# fmc_digital_io_front_panel.net
KiCad netlist of a schematic drawn in Altium Designer
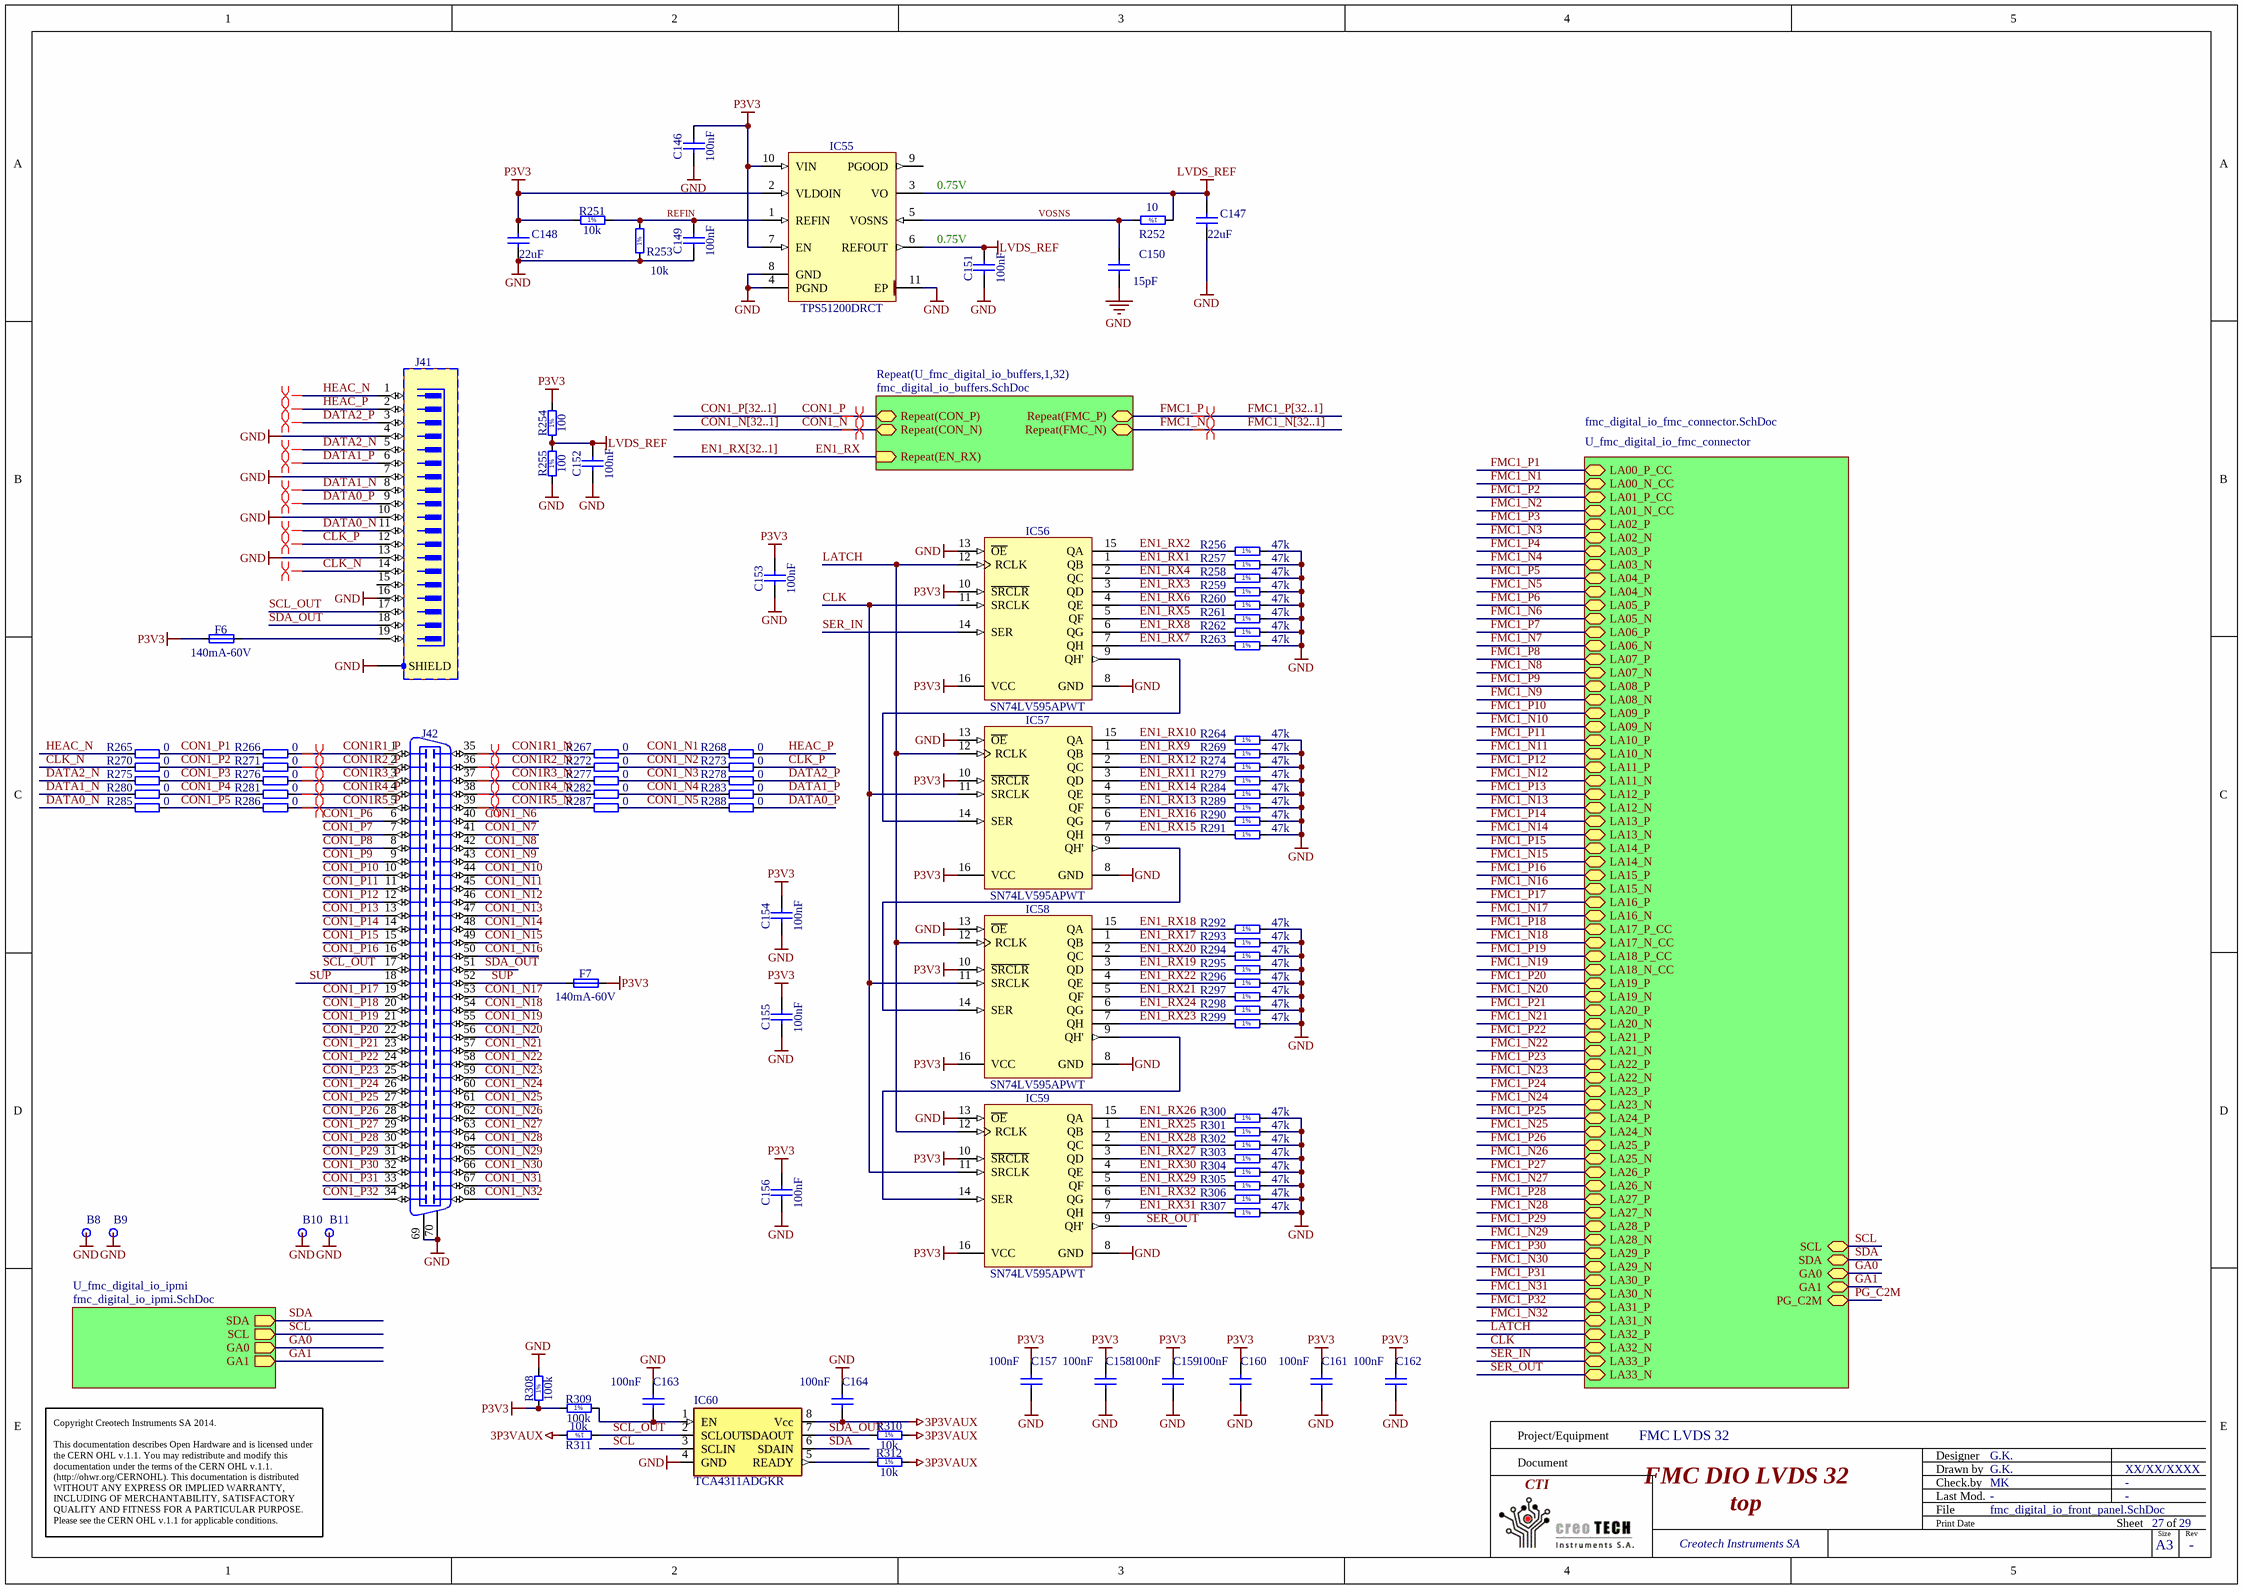
[diagram p0: fmc_digital_io_front_panel.SchDoc]

(export (version "E")
  (design (tool "Eeschema 10.0.6"))
  (components
    (comp (ref "B8")
      (value "Plated Hole")
      (footprint "MTG300_600")
      (description "Single Terminal Socket")
      (fields (field (name "PART NUMBER") "PLATED_HOLE3.0_PAD6.0") (field (name "AUTHOR") "CERN DEM JLC"))
      (libsource (lib "Eletro-mechanical") (part "Single Terminal Socket"))
    )
    (comp (ref "B9")
      (value "Plated Hole")
      (footprint "MTG300_600")
      (description "Single Terminal Socket")
      (fields (field (name "PART NUMBER") "PLATED_HOLE3.0_PAD6.0") (field (name "AUTHOR") "CERN DEM JLC"))
      (libsource (lib "Eletro-mechanical") (part "Single Terminal Socket"))
    )
    (comp (ref "B10")
      (value "Plated Hole")
      (footprint "MTG300_600")
      (description "Single Terminal Socket")
      (fields (field (name "PART NUMBER") "PLATED_HOLE3.0_PAD6.0") (field (name "AUTHOR") "CERN DEM JLC"))
      (libsource (lib "Eletro-mechanical") (part "Single Terminal Socket"))
    )
    (comp (ref "B11")
      (value "Plated Hole")
      (footprint "MTG300_600")
      (description "Single Terminal Socket")
      (fields (field (name "PART NUMBER") "PLATED_HOLE3.0_PAD6.0") (field (name "AUTHOR") "CERN DEM JLC"))
      (libsource (lib "Eletro-mechanical") (part "Single Terminal Socket"))
    )
    (comp (ref "C146")
      (value "100nF")
      (footprint "CAPC1005X55N")
      (description "Non-polarised capacitor")
      (fields
        (field (name "PART NUMBER") "CC0402_100NF_16V_10%_X5R")
        (field (name "VOLTAGE") "16V")
        (field (name "AUTHOR") "CERN DEM JLC")
      )
      (libsource (lib "Capacitors") (part "Capacitor - non polarized"))
    )
    (comp (ref "C147")
      (value "22uF")
      (footprint "CAPC3216X180N")
      (description "Non-polarised capacitor")
      (fields
        (field (name "PART NUMBER") "CC1206_22UF_10V_10%_X7R")
        (field (name "VOLTAGE") "10V")
        (field (name "AUTHOR") "CERN DEM JLC")
      )
      (libsource (lib "Capacitors") (part "Capacitor - non polarized"))
    )
    (comp (ref "C148")
      (value "22uF")
      (footprint "CAPC3216X180N")
      (description "Non-polarised capacitor")
      (fields
        (field (name "PART NUMBER") "CC1206_22UF_10V_10%_X7R")
        (field (name "VOLTAGE") "10V")
        (field (name "AUTHOR") "CERN DEM JLC")
      )
      (libsource (lib "Capacitors") (part "Capacitor - non polarized"))
    )
    (comp (ref "C149")
      (value "100nF")
      (footprint "CAPC1005X55N")
      (description "Non-polarised capacitor")
      (fields
        (field (name "PART NUMBER") "CC0402_100NF_16V_10%_X5R")
        (field (name "VOLTAGE") "16V")
        (field (name "AUTHOR") "CERN DEM JLC")
      )
      (libsource (lib "Capacitors") (part "Capacitor - non polarized"))
    )
    (comp (ref "C150")
      (value "15pF")
      (footprint "CAPC1005X55N")
      (description "Non-polarised capacitor")
      (fields
        (field (name "PART NUMBER") "CC0402_15PF_50V_5%_NP0")
        (field (name "VOLTAGE") "50V")
        (field (name "AUTHOR") "CERN DEM JLC")
      )
      (libsource (lib "Capacitors") (part "Capacitor - non polarized"))
    )
    (comp (ref "C151")
      (value "100nF")
      (footprint "CAPC1005X55N")
      (description "Non-polarised capacitor")
      (fields
        (field (name "PART NUMBER") "CC0402_100NF_16V_10%_X5R")
        (field (name "VOLTAGE") "16V")
        (field (name "AUTHOR") "CERN DEM JLC")
      )
      (libsource (lib "Capacitors") (part "Capacitor - non polarized"))
    )
    (comp (ref "C152")
      (value "100nF")
      (footprint "CAPC1005X55N")
      (description "Non-polarised capacitor")
      (fields
        (field (name "PART NUMBER") "CC0402_100NF_16V_10%_X5R")
        (field (name "VOLTAGE") "16V")
        (field (name "AUTHOR") "CERN DEM JLC")
      )
      (libsource (lib "Capacitors") (part "Capacitor - non polarized"))
    )
    (comp (ref "C153")
      (value "100nF")
      (footprint "CAPC1005X55N")
      (description "Non-polarised capacitor")
      (fields
        (field (name "PART NUMBER") "CC0402_100NF_16V_10%_X5R")
        (field (name "VOLTAGE") "16V")
        (field (name "AUTHOR") "CERN DEM JLC")
      )
      (libsource (lib "Capacitors") (part "Capacitor - non polarized"))
    )
    (comp (ref "C154")
      (value "100nF")
      (footprint "CAPC1005X55N")
      (description "Non-polarised capacitor")
      (fields
        (field (name "PART NUMBER") "CC0402_100NF_16V_10%_X5R")
        (field (name "VOLTAGE") "16V")
        (field (name "AUTHOR") "CERN DEM JLC")
      )
      (libsource (lib "Capacitors") (part "Capacitor - non polarized"))
    )
    (comp (ref "C155")
      (value "100nF")
      (footprint "CAPC1005X55N")
      (description "Non-polarised capacitor")
      (fields
        (field (name "PART NUMBER") "CC0402_100NF_16V_10%_X5R")
        (field (name "VOLTAGE") "16V")
        (field (name "AUTHOR") "CERN DEM JLC")
      )
      (libsource (lib "Capacitors") (part "Capacitor - non polarized"))
    )
    (comp (ref "C156")
      (value "100nF")
      (footprint "CAPC1005X55N")
      (description "Non-polarised capacitor")
      (fields
        (field (name "PART NUMBER") "CC0402_100NF_16V_10%_X5R")
        (field (name "VOLTAGE") "16V")
        (field (name "AUTHOR") "CERN DEM JLC")
      )
      (libsource (lib "Capacitors") (part "Capacitor - non polarized"))
    )
    (comp (ref "C157")
      (value "100nF")
      (footprint "CAPC1005X55N")
      (description "Non-polarised capacitor")
      (fields
        (field (name "PART NUMBER") "CC0402_100NF_16V_10%_X7R")
        (field (name "VOLTAGE") "16V")
        (field (name "AUTHOR") "CERN DEM JLC")
      )
      (libsource (lib "Capacitors") (part "Capacitor - non polarized"))
    )
    (comp (ref "C158")
      (value "100nF")
      (footprint "CAPC1005X55N")
      (description "Non-polarised capacitor")
      (fields
        (field (name "PART NUMBER") "CC0402_100NF_16V_10%_X7R")
        (field (name "VOLTAGE") "16V")
        (field (name "AUTHOR") "CERN DEM JLC")
      )
      (libsource (lib "Capacitors") (part "Capacitor - non polarized"))
    )
    (comp (ref "C159")
      (value "100nF")
      (footprint "CAPC1005X55N")
      (description "Non-polarised capacitor")
      (fields
        (field (name "PART NUMBER") "CC0402_100NF_16V_10%_X7R")
        (field (name "VOLTAGE") "16V")
        (field (name "AUTHOR") "CERN DEM JLC")
      )
      (libsource (lib "Capacitors") (part "Capacitor - non polarized"))
    )
    (comp (ref "C160")
      (value "100nF")
      (footprint "CAPC1005X55N")
      (description "Non-polarised capacitor")
      (fields
        (field (name "PART NUMBER") "CC0402_100NF_16V_10%_X7R")
        (field (name "VOLTAGE") "16V")
        (field (name "AUTHOR") "CERN DEM JLC")
      )
      (libsource (lib "Capacitors") (part "Capacitor - non polarized"))
    )
    (comp (ref "C161")
      (value "100nF")
      (footprint "CAPC1005X55N")
      (description "Non-polarised capacitor")
      (fields
        (field (name "PART NUMBER") "CC0402_100NF_16V_10%_X7R")
        (field (name "VOLTAGE") "16V")
        (field (name "AUTHOR") "CERN DEM JLC")
      )
      (libsource (lib "Capacitors") (part "Capacitor - non polarized"))
    )
    (comp (ref "C162")
      (value "100nF")
      (footprint "CAPC1005X55N")
      (description "Non-polarised capacitor")
      (fields
        (field (name "PART NUMBER") "CC0402_100NF_16V_10%_X7R")
        (field (name "VOLTAGE") "16V")
        (field (name "AUTHOR") "CERN DEM JLC")
      )
      (libsource (lib "Capacitors") (part "Capacitor - non polarized"))
    )
    (comp (ref "C163")
      (value "100nF")
      (footprint "CAPC1005X55N")
      (description "Non-polarised capacitor")
      (fields
        (field (name "PART NUMBER") "CC0402_100NF_16V_10%_X7R")
        (field (name "VOLTAGE") "16V")
        (field (name "AUTHOR") "CERN DEM JLC")
      )
      (libsource (lib "Capacitors") (part "Capacitor - non polarized"))
    )
    (comp (ref "C164")
      (value "100nF")
      (footprint "CAPC1005X55N")
      (description "Non-polarised capacitor")
      (fields
        (field (name "PART NUMBER") "CC0402_100NF_16V_10%_X7R")
        (field (name "VOLTAGE") "16V")
        (field (name "AUTHOR") "CERN DEM JLC")
      )
      (libsource (lib "Capacitors") (part "Capacitor - non polarized"))
    )
    (comp (ref "F6")
      (value "140mA-60V")
      (footprint "FUSRC4632X90N")
      (description "Fuse")
      (fields
        (field (name "PART NUMBER") "FUSR1812_TYCO-MINISMDC014F")
        (field (name "MANUFACTURER") "TYCO ELECTRONICS")
        (field (name "AUTHOR") "CERN DEM JLC")
      )
      (libsource (lib "Eletro-mechanical") (part "Fuse"))
    )
    (comp (ref "F7")
      (value "140mA-60V")
      (footprint "FUSRC4632X90N")
      (description "Fuse")
      (fields
        (field (name "PART NUMBER") "FUSR1812_TYCO-MINISMDC014F")
        (field (name "MANUFACTURER") "TYCO ELECTRONICS")
        (field (name "AUTHOR") "CERN DEM JLC")
      )
      (libsource (lib "Eletro-mechanical") (part "Fuse"))
    )
    (comp (ref "IC55")
      (value "TPS51200DRCT")
      (footprint "TEXAS_DRC (S-PVSON-N10)")
      (description "Sink/Source DDR Termination Regulator")
      (fields (field (name "MANUFACTURER") "TEXAS INSTRUMENTS") (field (name "AUTHOR") "CERN DEM JLC"))
      (libsource (lib "ICs And Semiconductors") (part "TPS51200DRC"))
    )
    (comp (ref "IC56")
      (value "SN74LV595APWT")
      (footprint "SOP65P640X120-16N")
      (description "8-Bit Shift Register With 3-State Output Register")
      (fields (field (name "MANUFACTURER") "TEXAS INSTRUMENTS") (field (name "AUTHOR") "CERN DEM JLC"))
      (libsource (lib "ICs And Semiconductors") (part "74595"))
    )
    (comp (ref "IC57")
      (value "SN74LV595APWT")
      (footprint "SOP65P640X120-16N")
      (description "8-Bit Shift Register With 3-State Output Register")
      (fields (field (name "MANUFACTURER") "TEXAS INSTRUMENTS") (field (name "AUTHOR") "CERN DEM JLC"))
      (libsource (lib "ICs And Semiconductors") (part "74595"))
    )
    (comp (ref "IC58")
      (value "SN74LV595APWT")
      (footprint "SOP65P640X120-16N")
      (description "8-Bit Shift Register With 3-State Output Register")
      (fields (field (name "MANUFACTURER") "TEXAS INSTRUMENTS") (field (name "AUTHOR") "CERN DEM JLC"))
      (libsource (lib "ICs And Semiconductors") (part "74595"))
    )
    (comp (ref "IC59")
      (value "SN74LV595APWT")
      (footprint "SOP65P640X120-16N")
      (description "8-Bit Shift Register With 3-State Output Register")
      (fields (field (name "MANUFACTURER") "TEXAS INSTRUMENTS") (field (name "AUTHOR") "CERN DEM JLC"))
      (libsource (lib "ICs And Semiconductors") (part "74595"))
    )
    (comp (ref "IC60")
      (value "TCA4311ADGKR")
      (footprint "msop-8")
      (description "HOT SWAPPABLE 2-WIRE BUS BUFFERS")
      (libsource (lib "LIBRARY_SCH") (part "IIC_TCA4311A"))
    )
    (comp (ref "J41")
      (value "HDMI")
      (footprint "MOLEX_46765-1001")
      (description "Connector HDMI 19 Male + 1 Shield")
      (fields
        (field (name "PART NUMBER") "MOLEX_46765-1001")
        (field (name "MANUFACTURER") "MOLEX")
        (field (name "AUTHOR") "CERN DEM JLC")
      )
      (libsource (lib "Connectors") (part "Connector HDMI 19 Male + 1 Shield"))
    )
    (comp (ref "J42")
      (value "DNP")
      (footprint "MOLEX_71430-0013")
      (description "Very High Density Cable Interconnect (VHDCI ) 68 Female")
      (fields
        (field (name "PART NUMBER") "MOLEX_71430-0013")
        (field (name "MANUFACTURER") "MOLEX")
        (field (name "AUTHOR") "CERN DEM JLC")
      )
      (libsource (lib "Connectors") (part "Connector VHDCI 68 Female"))
    )
    (comp (ref "R251")
      (value "10k")
      (footprint "RESC1005X40N")
      (description "Resistor - 1%")
      (fields
        (field (name "PART NUMBER") "R0402_10K_1%_0.0625W_100PPM")
        (field (name "POWER") "0.0625W")
        (field (name "AUTHOR") "CERN DEM JLC")
      )
      (libsource (lib "Resistors") (part "Resistor - 1%"))
    )
    (comp (ref "R252")
      (value "10")
      (footprint "RESC1005X40N")
      (description "Resistor - 1%")
      (fields
        (field (name "PART NUMBER") "R0402_10R_1%_0.0625W_200PPM")
        (field (name "POWER") "0.0625W")
        (field (name "AUTHOR") "CERN DEM JLC")
      )
      (libsource (lib "Resistors") (part "Resistor - 1%"))
    )
    (comp (ref "R253")
      (value "10k")
      (footprint "RESC1005X40N")
      (description "Resistor - 1%")
      (fields
        (field (name "PART NUMBER") "R0402_10K_1%_0.0625W_100PPM")
        (field (name "POWER") "0.0625W")
        (field (name "AUTHOR") "CERN DEM JLC")
      )
      (libsource (lib "Resistors") (part "Resistor - 1%"))
    )
    (comp (ref "R254")
      (value "100")
      (footprint "RESC1005X40N")
      (description "Resistor - 1%")
      (fields
        (field (name "PART NUMBER") "R0402_100R_1%_0.0625W_100PPM")
        (field (name "POWER") "0.0625W")
        (field (name "AUTHOR") "CERN DEM JLC")
      )
      (libsource (lib "Resistors") (part "Resistor - 1%"))
    )
    (comp (ref "R255")
      (value "100")
      (footprint "RESC1005X40N")
      (description "Resistor - 1%")
      (fields
        (field (name "PART NUMBER") "R0402_100R_1%_0.0625W_100PPM")
        (field (name "POWER") "0.0625W")
        (field (name "AUTHOR") "CERN DEM JLC")
      )
      (libsource (lib "Resistors") (part "Resistor - 1%"))
    )
    (comp (ref "R256")
      (value "47k")
      (footprint "RESC1005X40N")
      (description "Resistor - 1%")
      (fields
        (field (name "PART NUMBER") "R0402_47K_1%_0.0625W_100PPM")
        (field (name "POWER") "0.0625W")
        (field (name "AUTHOR") "CERN DEM JLC")
      )
      (libsource (lib "Resistors") (part "Resistor - 1%"))
    )
    (comp (ref "R257")
      (value "47k")
      (footprint "RESC1005X40N")
      (description "Resistor - 1%")
      (fields
        (field (name "PART NUMBER") "R0402_47K_1%_0.0625W_100PPM")
        (field (name "POWER") "0.0625W")
        (field (name "AUTHOR") "CERN DEM JLC")
      )
      (libsource (lib "Resistors") (part "Resistor - 1%"))
    )
    (comp (ref "R258")
      (value "47k")
      (footprint "RESC1005X40N")
      (description "Resistor - 1%")
      (fields
        (field (name "PART NUMBER") "R0402_47K_1%_0.0625W_100PPM")
        (field (name "POWER") "0.0625W")
        (field (name "AUTHOR") "CERN DEM JLC")
      )
      (libsource (lib "Resistors") (part "Resistor - 1%"))
    )
    (comp (ref "R259")
      (value "47k")
      (footprint "RESC1005X40N")
      (description "Resistor - 1%")
      (fields
        (field (name "PART NUMBER") "R0402_47K_1%_0.0625W_100PPM")
        (field (name "POWER") "0.0625W")
        (field (name "AUTHOR") "CERN DEM JLC")
      )
      (libsource (lib "Resistors") (part "Resistor - 1%"))
    )
    (comp (ref "R260")
      (value "47k")
      (footprint "RESC1005X40N")
      (description "Resistor - 1%")
      (fields
        (field (name "PART NUMBER") "R0402_47K_1%_0.0625W_100PPM")
        (field (name "POWER") "0.0625W")
        (field (name "AUTHOR") "CERN DEM JLC")
      )
      (libsource (lib "Resistors") (part "Resistor - 1%"))
    )
    (comp (ref "R261")
      (value "47k")
      (footprint "RESC1005X40N")
      (description "Resistor - 1%")
      (fields
        (field (name "PART NUMBER") "R0402_47K_1%_0.0625W_100PPM")
        (field (name "POWER") "0.0625W")
        (field (name "AUTHOR") "CERN DEM JLC")
      )
      (libsource (lib "Resistors") (part "Resistor - 1%"))
    )
    (comp (ref "R262")
      (value "47k")
      (footprint "RESC1005X40N")
      (description "Resistor - 1%")
      (fields
        (field (name "PART NUMBER") "R0402_47K_1%_0.0625W_100PPM")
        (field (name "POWER") "0.0625W")
        (field (name "AUTHOR") "CERN DEM JLC")
      )
      (libsource (lib "Resistors") (part "Resistor - 1%"))
    )
    (comp (ref "R263")
      (value "47k")
      (footprint "RESC1005X40N")
      (description "Resistor - 1%")
      (fields
        (field (name "PART NUMBER") "R0402_47K_1%_0.0625W_100PPM")
        (field (name "POWER") "0.0625W")
        (field (name "AUTHOR") "CERN DEM JLC")
      )
      (libsource (lib "Resistors") (part "Resistor - 1%"))
    )
    (comp (ref "R264")
      (value "47k")
      (footprint "RESC1005X40N")
      (description "Resistor - 1%")
      (fields
        (field (name "PART NUMBER") "R0402_47K_1%_0.0625W_100PPM")
        (field (name "POWER") "0.0625W")
        (field (name "AUTHOR") "CERN DEM JLC")
      )
      (libsource (lib "Resistors") (part "Resistor - 1%"))
    )
    (comp (ref "R265")
      (value "0")
      (footprint "RESC1005X40N")
      (description "Resistor")
      (fields
        (field (name "PART NUMBER") "R0402_0R_JUMPER")
        (field (name "MANUFACTURER") "GENERIC")
        (field (name "AUTHOR") "CERN DEM JLC")
      )
      (libsource (lib "Resistors") (part "Resistor"))
    )
    (comp (ref "R266")
      (value "0")
      (footprint "RESC1005X40N")
      (description "Resistor")
      (fields
        (field (name "PART NUMBER") "R0402_0R_JUMPER")
        (field (name "MANUFACTURER") "GENERIC")
        (field (name "AUTHOR") "CERN DEM JLC")
      )
      (libsource (lib "Resistors") (part "Resistor"))
    )
    (comp (ref "R267")
      (value "0")
      (footprint "RESC1005X40N")
      (description "Resistor")
      (fields
        (field (name "PART NUMBER") "R0402_0R_JUMPER")
        (field (name "MANUFACTURER") "GENERIC")
        (field (name "AUTHOR") "CERN DEM JLC")
      )
      (libsource (lib "Resistors") (part "Resistor"))
    )
    (comp (ref "R268")
      (value "0")
      (footprint "RESC1005X40N")
      (description "Resistor")
      (fields
        (field (name "PART NUMBER") "R0402_0R_JUMPER")
        (field (name "MANUFACTURER") "GENERIC")
        (field (name "AUTHOR") "CERN DEM JLC")
      )
      (libsource (lib "Resistors") (part "Resistor"))
    )
    (comp (ref "R269")
      (value "47k")
      (footprint "RESC1005X40N")
      (description "Resistor - 1%")
      (fields
        (field (name "PART NUMBER") "R0402_47K_1%_0.0625W_100PPM")
        (field (name "POWER") "0.0625W")
        (field (name "AUTHOR") "CERN DEM JLC")
      )
      (libsource (lib "Resistors") (part "Resistor - 1%"))
    )
    (comp (ref "R270")
      (value "0")
      (footprint "RESC1005X40N")
      (description "Resistor")
      (fields
        (field (name "PART NUMBER") "R0402_0R_JUMPER")
        (field (name "MANUFACTURER") "GENERIC")
        (field (name "AUTHOR") "CERN DEM JLC")
      )
      (libsource (lib "Resistors") (part "Resistor"))
    )
    (comp (ref "R271")
      (value "0")
      (footprint "RESC1005X40N")
      (description "Resistor")
      (fields
        (field (name "PART NUMBER") "R0402_0R_JUMPER")
        (field (name "MANUFACTURER") "GENERIC")
        (field (name "AUTHOR") "CERN DEM JLC")
      )
      (libsource (lib "Resistors") (part "Resistor"))
    )
    (comp (ref "R272")
      (value "0")
      (footprint "RESC1005X40N")
      (description "Resistor")
      (fields
        (field (name "PART NUMBER") "R0402_0R_JUMPER")
        (field (name "MANUFACTURER") "GENERIC")
        (field (name "AUTHOR") "CERN DEM JLC")
      )
      (libsource (lib "Resistors") (part "Resistor"))
    )
    (comp (ref "R273")
      (value "0")
      (footprint "RESC1005X40N")
      (description "Resistor")
      (fields
        (field (name "PART NUMBER") "R0402_0R_JUMPER")
        (field (name "MANUFACTURER") "GENERIC")
        (field (name "AUTHOR") "CERN DEM JLC")
      )
      (libsource (lib "Resistors") (part "Resistor"))
    )
    (comp (ref "R274")
      (value "47k")
      (footprint "RESC1005X40N")
      (description "Resistor - 1%")
      (fields
        (field (name "PART NUMBER") "R0402_47K_1%_0.0625W_100PPM")
        (field (name "POWER") "0.0625W")
        (field (name "AUTHOR") "CERN DEM JLC")
      )
      (libsource (lib "Resistors") (part "Resistor - 1%"))
    )
    (comp (ref "R275")
      (value "0")
      (footprint "RESC1005X40N")
      (description "Resistor")
      (fields
        (field (name "PART NUMBER") "R0402_0R_JUMPER")
        (field (name "MANUFACTURER") "GENERIC")
        (field (name "AUTHOR") "CERN DEM JLC")
      )
      (libsource (lib "Resistors") (part "Resistor"))
    )
    (comp (ref "R276")
      (value "0")
      (footprint "RESC1005X40N")
      (description "Resistor")
      (fields
        (field (name "PART NUMBER") "R0402_0R_JUMPER")
        (field (name "MANUFACTURER") "GENERIC")
        (field (name "AUTHOR") "CERN DEM JLC")
      )
      (libsource (lib "Resistors") (part "Resistor"))
    )
    (comp (ref "R277")
      (value "0")
      (footprint "RESC1005X40N")
      (description "Resistor")
      (fields
        (field (name "PART NUMBER") "R0402_0R_JUMPER")
        (field (name "MANUFACTURER") "GENERIC")
        (field (name "AUTHOR") "CERN DEM JLC")
      )
      (libsource (lib "Resistors") (part "Resistor"))
    )
    (comp (ref "R278")
      (value "0")
      (footprint "RESC1005X40N")
      (description "Resistor")
      (fields
        (field (name "PART NUMBER") "R0402_0R_JUMPER")
        (field (name "MANUFACTURER") "GENERIC")
        (field (name "AUTHOR") "CERN DEM JLC")
      )
      (libsource (lib "Resistors") (part "Resistor"))
    )
    (comp (ref "R279")
      (value "47k")
      (footprint "RESC1005X40N")
      (description "Resistor - 1%")
      (fields
        (field (name "PART NUMBER") "R0402_47K_1%_0.0625W_100PPM")
        (field (name "POWER") "0.0625W")
        (field (name "AUTHOR") "CERN DEM JLC")
      )
      (libsource (lib "Resistors") (part "Resistor - 1%"))
    )
    (comp (ref "R280")
      (value "0")
      (footprint "RESC1005X40N")
      (description "Resistor")
      (fields
        (field (name "PART NUMBER") "R0402_0R_JUMPER")
        (field (name "MANUFACTURER") "GENERIC")
        (field (name "AUTHOR") "CERN DEM JLC")
      )
      (libsource (lib "Resistors") (part "Resistor"))
    )
    (comp (ref "R281")
      (value "0")
      (footprint "RESC1005X40N")
      (description "Resistor")
      (fields
        (field (name "PART NUMBER") "R0402_0R_JUMPER")
        (field (name "MANUFACTURER") "GENERIC")
        (field (name "AUTHOR") "CERN DEM JLC")
      )
      (libsource (lib "Resistors") (part "Resistor"))
    )
    (comp (ref "R282")
      (value "0")
      (footprint "RESC1005X40N")
      (description "Resistor")
      (fields
        (field (name "PART NUMBER") "R0402_0R_JUMPER")
        (field (name "MANUFACTURER") "GENERIC")
        (field (name "AUTHOR") "CERN DEM JLC")
      )
      (libsource (lib "Resistors") (part "Resistor"))
    )
    (comp (ref "R283")
      (value "0")
      (footprint "RESC1005X40N")
      (description "Resistor")
      (fields
        (field (name "PART NUMBER") "R0402_0R_JUMPER")
        (field (name "MANUFACTURER") "GENERIC")
        (field (name "AUTHOR") "CERN DEM JLC")
      )
      (libsource (lib "Resistors") (part "Resistor"))
    )
    (comp (ref "R284")
      (value "47k")
      (footprint "RESC1005X40N")
      (description "Resistor - 1%")
      (fields
        (field (name "PART NUMBER") "R0402_47K_1%_0.0625W_100PPM")
        (field (name "POWER") "0.0625W")
        (field (name "AUTHOR") "CERN DEM JLC")
      )
      (libsource (lib "Resistors") (part "Resistor - 1%"))
    )
    (comp (ref "R285")
      (value "0")
      (footprint "RESC1005X40N")
      (description "Resistor")
      (fields
        (field (name "PART NUMBER") "R0402_0R_JUMPER")
        (field (name "MANUFACTURER") "GENERIC")
        (field (name "AUTHOR") "CERN DEM JLC")
      )
      (libsource (lib "Resistors") (part "Resistor"))
    )
    (comp (ref "R286")
      (value "0")
      (footprint "RESC1005X40N")
      (description "Resistor")
      (fields
        (field (name "PART NUMBER") "R0402_0R_JUMPER")
        (field (name "MANUFACTURER") "GENERIC")
        (field (name "AUTHOR") "CERN DEM JLC")
      )
      (libsource (lib "Resistors") (part "Resistor"))
    )
    (comp (ref "R287")
      (value "0")
      (footprint "RESC1005X40N")
      (description "Resistor")
      (fields
        (field (name "PART NUMBER") "R0402_0R_JUMPER")
        (field (name "MANUFACTURER") "GENERIC")
        (field (name "AUTHOR") "CERN DEM JLC")
      )
      (libsource (lib "Resistors") (part "Resistor"))
    )
    (comp (ref "R288")
      (value "0")
      (footprint "RESC1005X40N")
      (description "Resistor")
      (fields
        (field (name "PART NUMBER") "R0402_0R_JUMPER")
        (field (name "MANUFACTURER") "GENERIC")
        (field (name "AUTHOR") "CERN DEM JLC")
      )
      (libsource (lib "Resistors") (part "Resistor"))
    )
    (comp (ref "R289")
      (value "47k")
      (footprint "RESC1005X40N")
      (description "Resistor - 1%")
      (fields
        (field (name "PART NUMBER") "R0402_47K_1%_0.0625W_100PPM")
        (field (name "POWER") "0.0625W")
        (field (name "AUTHOR") "CERN DEM JLC")
      )
      (libsource (lib "Resistors") (part "Resistor - 1%"))
    )
    (comp (ref "R290")
      (value "47k")
      (footprint "RESC1005X40N")
      (description "Resistor - 1%")
      (fields
        (field (name "PART NUMBER") "R0402_47K_1%_0.0625W_100PPM")
        (field (name "POWER") "0.0625W")
        (field (name "AUTHOR") "CERN DEM JLC")
      )
      (libsource (lib "Resistors") (part "Resistor - 1%"))
    )
    (comp (ref "R291")
      (value "47k")
      (footprint "RESC1005X40N")
      (description "Resistor - 1%")
      (fields
        (field (name "PART NUMBER") "R0402_47K_1%_0.0625W_100PPM")
        (field (name "POWER") "0.0625W")
        (field (name "AUTHOR") "CERN DEM JLC")
      )
      (libsource (lib "Resistors") (part "Resistor - 1%"))
    )
    (comp (ref "R292")
      (value "47k")
      (footprint "RESC1005X40N")
      (description "Resistor - 1%")
      (fields
        (field (name "PART NUMBER") "R0402_47K_1%_0.0625W_100PPM")
        (field (name "POWER") "0.0625W")
        (field (name "AUTHOR") "CERN DEM JLC")
      )
      (libsource (lib "Resistors") (part "Resistor - 1%"))
    )
    (comp (ref "R293")
      (value "47k")
      (footprint "RESC1005X40N")
      (description "Resistor - 1%")
      (fields
        (field (name "PART NUMBER") "R0402_47K_1%_0.0625W_100PPM")
        (field (name "POWER") "0.0625W")
        (field (name "AUTHOR") "CERN DEM JLC")
      )
      (libsource (lib "Resistors") (part "Resistor - 1%"))
    )
    (comp (ref "R294")
      (value "47k")
      (footprint "RESC1005X40N")
      (description "Resistor - 1%")
      (fields
        (field (name "PART NUMBER") "R0402_47K_1%_0.0625W_100PPM")
        (field (name "POWER") "0.0625W")
        (field (name "AUTHOR") "CERN DEM JLC")
      )
      (libsource (lib "Resistors") (part "Resistor - 1%"))
    )
    (comp (ref "R295")
      (value "47k")
      (footprint "RESC1005X40N")
      (description "Resistor - 1%")
      (fields
        (field (name "PART NUMBER") "R0402_47K_1%_0.0625W_100PPM")
        (field (name "POWER") "0.0625W")
        (field (name "AUTHOR") "CERN DEM JLC")
      )
      (libsource (lib "Resistors") (part "Resistor - 1%"))
    )
    (comp (ref "R296")
      (value "47k")
      (footprint "RESC1005X40N")
      (description "Resistor - 1%")
      (fields
        (field (name "PART NUMBER") "R0402_47K_1%_0.0625W_100PPM")
        (field (name "POWER") "0.0625W")
        (field (name "AUTHOR") "CERN DEM JLC")
      )
      (libsource (lib "Resistors") (part "Resistor - 1%"))
    )
    (comp (ref "R297")
      (value "47k")
      (footprint "RESC1005X40N")
      (description "Resistor - 1%")
      (fields
        (field (name "PART NUMBER") "R0402_47K_1%_0.0625W_100PPM")
        (field (name "POWER") "0.0625W")
        (field (name "AUTHOR") "CERN DEM JLC")
      )
      (libsource (lib "Resistors") (part "Resistor - 1%"))
    )
    (comp (ref "R298")
      (value "47k")
      (footprint "RESC1005X40N")
      (description "Resistor - 1%")
      (fields
        (field (name "PART NUMBER") "R0402_47K_1%_0.0625W_100PPM")
        (field (name "POWER") "0.0625W")
        (field (name "AUTHOR") "CERN DEM JLC")
      )
      (libsource (lib "Resistors") (part "Resistor - 1%"))
    )
    (comp (ref "R299")
      (value "47k")
      (footprint "RESC1005X40N")
      (description "Resistor - 1%")
      (fields
        (field (name "PART NUMBER") "R0402_47K_1%_0.0625W_100PPM")
        (field (name "POWER") "0.0625W")
        (field (name "AUTHOR") "CERN DEM JLC")
      )
      (libsource (lib "Resistors") (part "Resistor - 1%"))
    )
    (comp (ref "R300")
      (value "47k")
      (footprint "RESC1005X40N")
      (description "Resistor - 1%")
      (fields
        (field (name "PART NUMBER") "R0402_47K_1%_0.0625W_100PPM")
        (field (name "POWER") "0.0625W")
        (field (name "AUTHOR") "CERN DEM JLC")
      )
      (libsource (lib "Resistors") (part "Resistor - 1%"))
    )
    (comp (ref "R301")
      (value "47k")
      (footprint "RESC1005X40N")
      (description "Resistor - 1%")
      (fields
        (field (name "PART NUMBER") "R0402_47K_1%_0.0625W_100PPM")
        (field (name "POWER") "0.0625W")
        (field (name "AUTHOR") "CERN DEM JLC")
      )
      (libsource (lib "Resistors") (part "Resistor - 1%"))
    )
    (comp (ref "R302")
      (value "47k")
      (footprint "RESC1005X40N")
      (description "Resistor - 1%")
      (fields
        (field (name "PART NUMBER") "R0402_47K_1%_0.0625W_100PPM")
        (field (name "POWER") "0.0625W")
        (field (name "AUTHOR") "CERN DEM JLC")
      )
      (libsource (lib "Resistors") (part "Resistor - 1%"))
    )
    (comp (ref "R303")
      (value "47k")
      (footprint "RESC1005X40N")
      (description "Resistor - 1%")
      (fields
        (field (name "PART NUMBER") "R0402_47K_1%_0.0625W_100PPM")
        (field (name "POWER") "0.0625W")
        (field (name "AUTHOR") "CERN DEM JLC")
      )
      (libsource (lib "Resistors") (part "Resistor - 1%"))
    )
    (comp (ref "R304")
      (value "47k")
      (footprint "RESC1005X40N")
      (description "Resistor - 1%")
      (fields
        (field (name "PART NUMBER") "R0402_47K_1%_0.0625W_100PPM")
        (field (name "POWER") "0.0625W")
        (field (name "AUTHOR") "CERN DEM JLC")
      )
      (libsource (lib "Resistors") (part "Resistor - 1%"))
    )
    (comp (ref "R305")
      (value "47k")
      (footprint "RESC1005X40N")
      (description "Resistor - 1%")
      (fields
        (field (name "PART NUMBER") "R0402_47K_1%_0.0625W_100PPM")
        (field (name "POWER") "0.0625W")
        (field (name "AUTHOR") "CERN DEM JLC")
      )
      (libsource (lib "Resistors") (part "Resistor - 1%"))
    )
    (comp (ref "R306")
      (value "47k")
      (footprint "RESC1005X40N")
      (description "Resistor - 1%")
      (fields
        (field (name "PART NUMBER") "R0402_47K_1%_0.0625W_100PPM")
        (field (name "POWER") "0.0625W")
        (field (name "AUTHOR") "CERN DEM JLC")
      )
      (libsource (lib "Resistors") (part "Resistor - 1%"))
    )
    (comp (ref "R307")
      (value "47k")
      (footprint "RESC1005X40N")
      (description "Resistor - 1%")
      (fields
        (field (name "PART NUMBER") "R0402_47K_1%_0.0625W_100PPM")
        (field (name "POWER") "0.0625W")
        (field (name "AUTHOR") "CERN DEM JLC")
      )
      (libsource (lib "Resistors") (part "Resistor - 1%"))
    )
    (comp (ref "R308")
      (value "100k")
      (footprint "RESC1005X40N")
      (description "Resistor - 1%")
      (fields
        (field (name "PART NUMBER") "R0402_100K_1%_0.0625W_100PPM")
        (field (name "POWER") "0.0625W")
        (field (name "AUTHOR") "CERN DEM JLC")
      )
      (libsource (lib "Resistors") (part "Resistor - 1%"))
    )
    (comp (ref "R309")
      (value "100k")
      (footprint "RESC1005X40N")
      (description "Resistor - 1%")
      (fields
        (field (name "PART NUMBER") "R0402_100K_1%_0.0625W_100PPM")
        (field (name "POWER") "0.0625W")
        (field (name "AUTHOR") "CERN DEM JLC")
      )
      (libsource (lib "Resistors") (part "Resistor - 1%"))
    )
    (comp (ref "R310")
      (value "10k")
      (footprint "RESC1005X40N")
      (description "Resistor - 1%")
      (fields
        (field (name "PART NUMBER") "R0402_10K_1%_0.0625W_100PPM")
        (field (name "POWER") "0.0625W")
        (field (name "AUTHOR") "CERN DEM JLC")
      )
      (libsource (lib "Resistors") (part "Resistor - 1%"))
    )
    (comp (ref "R311")
      (value "10k")
      (footprint "RESC1005X40N")
      (description "Resistor - 1%")
      (fields
        (field (name "PART NUMBER") "R0402_10K_1%_0.0625W_100PPM")
        (field (name "POWER") "0.0625W")
        (field (name "AUTHOR") "CERN DEM JLC")
      )
      (libsource (lib "Resistors") (part "Resistor - 1%"))
    )
    (comp (ref "R312")
      (value "10k")
      (footprint "RESC1005X40N")
      (description "Resistor - 1%")
      (fields
        (field (name "PART NUMBER") "R0402_10K_1%_0.0625W_100PPM")
        (field (name "POWER") "0.0625W")
        (field (name "AUTHOR") "CERN DEM JLC")
      )
      (libsource (lib "Resistors") (part "Resistor - 1%"))
    )
  )
  (nets
    (net (code "1") (name "/CLK") (class "Default")
      (node (ref "IC56") (pin "11") (pinfunction "SRCLK_11") (pintype "input"))
      (node (ref "IC57") (pin "11") (pinfunction "SRCLK_11") (pintype "input"))
      (node (ref "IC58") (pin "11") (pinfunction "SRCLK_11") (pintype "input"))
      (node (ref "IC59") (pin "11") (pinfunction "SRCLK_11") (pintype "input"))
    )
    (net (code "2") (name "/CLK_N") (class "Default")
      (node (ref "J41") (pin "14") (pinfunction "14_14") (pintype "bidirectional"))
      (node (ref "R270") (pin "1") (pinfunction "1_1") (pintype "passive"))
    )
    (net (code "3") (name "/CLK_P") (class "Default")
      (node (ref "J41") (pin "12") (pinfunction "12_12") (pintype "bidirectional"))
      (node (ref "R273") (pin "2") (pinfunction "2_2") (pintype "passive"))
    )
    (net (code "4") (name "/CON1R1_N") (class "Default")
      (node (ref "J42") (pin "35") (pinfunction "35_35") (pintype "bidirectional"))
      (node (ref "R267") (pin "1") (pinfunction "1_1") (pintype "passive"))
    )
    (net (code "5") (name "/CON1R1_P") (class "Default")
      (node (ref "J42") (pin "1") (pinfunction "1_1") (pintype "bidirectional"))
      (node (ref "R266") (pin "2") (pinfunction "2_2") (pintype "passive"))
    )
    (net (code "6") (name "/CON1R2_N") (class "Default")
      (node (ref "J42") (pin "36") (pinfunction "36_36") (pintype "bidirectional"))
      (node (ref "R272") (pin "1") (pinfunction "1_1") (pintype "passive"))
    )
    (net (code "7") (name "/CON1R2_P") (class "Default")
      (node (ref "J42") (pin "2") (pinfunction "2_2") (pintype "bidirectional"))
      (node (ref "R271") (pin "2") (pinfunction "2_2") (pintype "passive"))
    )
    (net (code "8") (name "/CON1R3_N") (class "Default")
      (node (ref "J42") (pin "37") (pinfunction "37_37") (pintype "bidirectional"))
      (node (ref "R277") (pin "1") (pinfunction "1_1") (pintype "passive"))
    )
    (net (code "9") (name "/CON1R3_P") (class "Default")
      (node (ref "J42") (pin "3") (pinfunction "3_3") (pintype "bidirectional"))
      (node (ref "R276") (pin "2") (pinfunction "2_2") (pintype "passive"))
    )
    (net (code "10") (name "/CON1R4_N") (class "Default")
      (node (ref "J42") (pin "38") (pinfunction "38_38") (pintype "bidirectional"))
      (node (ref "R282") (pin "1") (pinfunction "1_1") (pintype "passive"))
    )
    (net (code "11") (name "/CON1R4_P") (class "Default")
      (node (ref "J42") (pin "4") (pinfunction "4_4") (pintype "bidirectional"))
      (node (ref "R281") (pin "2") (pinfunction "2_2") (pintype "passive"))
    )
    (net (code "12") (name "/CON1R5_N") (class "Default")
      (node (ref "J42") (pin "39") (pinfunction "39_39") (pintype "bidirectional"))
      (node (ref "R287") (pin "1") (pinfunction "1_1") (pintype "passive"))
    )
    (net (code "13") (name "/CON1R5_P") (class "Default")
      (node (ref "J42") (pin "5") (pinfunction "5_5") (pintype "bidirectional"))
      (node (ref "R286") (pin "2") (pinfunction "2_2") (pintype "passive"))
    )
    (net (code "15") (name "/CON1_N1") (class "Default")
      (node (ref "R267") (pin "2") (pinfunction "2_2") (pintype "passive"))
      (node (ref "R268") (pin "1") (pinfunction "1_1") (pintype "passive"))
    )
    (net (code "16") (name "/CON1_N2") (class "Default")
      (node (ref "R272") (pin "2") (pinfunction "2_2") (pintype "passive"))
      (node (ref "R273") (pin "1") (pinfunction "1_1") (pintype "passive"))
    )
    (net (code "17") (name "/CON1_N3") (class "Default")
      (node (ref "R277") (pin "2") (pinfunction "2_2") (pintype "passive"))
      (node (ref "R278") (pin "1") (pinfunction "1_1") (pintype "passive"))
    )
    (net (code "18") (name "/CON1_N4") (class "Default")
      (node (ref "R282") (pin "2") (pinfunction "2_2") (pintype "passive"))
      (node (ref "R283") (pin "1") (pinfunction "1_1") (pintype "passive"))
    )
    (net (code "19") (name "/CON1_N5") (class "Default")
      (node (ref "R287") (pin "2") (pinfunction "2_2") (pintype "passive"))
      (node (ref "R288") (pin "1") (pinfunction "1_1") (pintype "passive"))
    )
    (net (code "20") (name "/CON1_N6") (class "Default")
      (node (ref "J42") (pin "40") (pinfunction "40_40") (pintype "bidirectional"))
    )
    (net (code "21") (name "/CON1_N7") (class "Default")
      (node (ref "J42") (pin "41") (pinfunction "41_41") (pintype "bidirectional"))
    )
    (net (code "22") (name "/CON1_N8") (class "Default")
      (node (ref "J42") (pin "42") (pinfunction "42_42") (pintype "bidirectional"))
    )
    (net (code "23") (name "/CON1_N9") (class "Default")
      (node (ref "J42") (pin "43") (pinfunction "43_43") (pintype "bidirectional"))
    )
    (net (code "24") (name "/CON1_N10") (class "Default")
      (node (ref "J42") (pin "44") (pinfunction "44_44") (pintype "bidirectional"))
    )
    (net (code "25") (name "/CON1_N11") (class "Default")
      (node (ref "J42") (pin "45") (pinfunction "45_45") (pintype "bidirectional"))
    )
    (net (code "26") (name "/CON1_N12") (class "Default")
      (node (ref "J42") (pin "46") (pinfunction "46_46") (pintype "bidirectional"))
    )
    (net (code "27") (name "/CON1_N13") (class "Default")
      (node (ref "J42") (pin "47") (pinfunction "47_47") (pintype "bidirectional"))
    )
    (net (code "28") (name "/CON1_N14") (class "Default")
      (node (ref "J42") (pin "48") (pinfunction "48_48") (pintype "bidirectional"))
    )
    (net (code "29") (name "/CON1_N15") (class "Default")
      (node (ref "J42") (pin "49") (pinfunction "49_49") (pintype "bidirectional"))
    )
    (net (code "30") (name "/CON1_N16") (class "Default")
      (node (ref "J42") (pin "50") (pinfunction "50_50") (pintype "bidirectional"))
    )
    (net (code "31") (name "/CON1_N17") (class "Default")
      (node (ref "J42") (pin "53") (pinfunction "53_53") (pintype "bidirectional"))
    )
    (net (code "32") (name "/CON1_N18") (class "Default")
      (node (ref "J42") (pin "54") (pinfunction "54_54") (pintype "bidirectional"))
    )
    (net (code "33") (name "/CON1_N19") (class "Default")
      (node (ref "J42") (pin "55") (pinfunction "55_55") (pintype "bidirectional"))
    )
    (net (code "34") (name "/CON1_N20") (class "Default")
      (node (ref "J42") (pin "56") (pinfunction "56_56") (pintype "bidirectional"))
    )
    (net (code "35") (name "/CON1_N21") (class "Default")
      (node (ref "J42") (pin "57") (pinfunction "57_57") (pintype "bidirectional"))
    )
    (net (code "36") (name "/CON1_N22") (class "Default")
      (node (ref "J42") (pin "58") (pinfunction "58_58") (pintype "bidirectional"))
    )
    (net (code "37") (name "/CON1_N23") (class "Default")
      (node (ref "J42") (pin "59") (pinfunction "59_59") (pintype "bidirectional"))
    )
    (net (code "38") (name "/CON1_N24") (class "Default")
      (node (ref "J42") (pin "60") (pinfunction "60_60") (pintype "bidirectional"))
    )
    (net (code "39") (name "/CON1_N25") (class "Default")
      (node (ref "J42") (pin "61") (pinfunction "61_61") (pintype "bidirectional"))
    )
    (net (code "40") (name "/CON1_N26") (class "Default")
      (node (ref "J42") (pin "62") (pinfunction "62_62") (pintype "bidirectional"))
    )
    (net (code "41") (name "/CON1_N27") (class "Default")
      (node (ref "J42") (pin "63") (pinfunction "63_63") (pintype "bidirectional"))
    )
    (net (code "42") (name "/CON1_N28") (class "Default")
      (node (ref "J42") (pin "64") (pinfunction "64_64") (pintype "bidirectional"))
    )
    (net (code "43") (name "/CON1_N29") (class "Default")
      (node (ref "J42") (pin "65") (pinfunction "65_65") (pintype "bidirectional"))
    )
    (net (code "44") (name "/CON1_N30") (class "Default")
      (node (ref "J42") (pin "66") (pinfunction "66_66") (pintype "bidirectional"))
    )
    (net (code "45") (name "/CON1_N31") (class "Default")
      (node (ref "J42") (pin "67") (pinfunction "67_67") (pintype "bidirectional"))
    )
    (net (code "46") (name "/CON1_N32") (class "Default")
      (node (ref "J42") (pin "68") (pinfunction "68_68") (pintype "bidirectional"))
    )
    (net (code "49") (name "/CON1_P1") (class "Default")
      (node (ref "R265") (pin "2") (pinfunction "2_2") (pintype "passive"))
      (node (ref "R266") (pin "1") (pinfunction "1_1") (pintype "passive"))
    )
    (net (code "50") (name "/CON1_P2") (class "Default")
      (node (ref "R270") (pin "2") (pinfunction "2_2") (pintype "passive"))
      (node (ref "R271") (pin "1") (pinfunction "1_1") (pintype "passive"))
    )
    (net (code "51") (name "/CON1_P3") (class "Default")
      (node (ref "R275") (pin "2") (pinfunction "2_2") (pintype "passive"))
      (node (ref "R276") (pin "1") (pinfunction "1_1") (pintype "passive"))
    )
    (net (code "52") (name "/CON1_P4") (class "Default")
      (node (ref "R280") (pin "2") (pinfunction "2_2") (pintype "passive"))
      (node (ref "R281") (pin "1") (pinfunction "1_1") (pintype "passive"))
    )
    (net (code "53") (name "/CON1_P5") (class "Default")
      (node (ref "R285") (pin "2") (pinfunction "2_2") (pintype "passive"))
      (node (ref "R286") (pin "1") (pinfunction "1_1") (pintype "passive"))
    )
    (net (code "54") (name "/CON1_P6") (class "Default")
      (node (ref "J42") (pin "6") (pinfunction "6_6") (pintype "bidirectional"))
    )
    (net (code "55") (name "/CON1_P7") (class "Default")
      (node (ref "J42") (pin "7") (pinfunction "7_7") (pintype "bidirectional"))
    )
    (net (code "56") (name "/CON1_P8") (class "Default")
      (node (ref "J42") (pin "8") (pinfunction "8_8") (pintype "bidirectional"))
    )
    (net (code "57") (name "/CON1_P9") (class "Default")
      (node (ref "J42") (pin "9") (pinfunction "9_9") (pintype "bidirectional"))
    )
    (net (code "58") (name "/CON1_P10") (class "Default")
      (node (ref "J42") (pin "10") (pinfunction "10_10") (pintype "bidirectional"))
    )
    (net (code "59") (name "/CON1_P11") (class "Default")
      (node (ref "J42") (pin "11") (pinfunction "11_11") (pintype "bidirectional"))
    )
    (net (code "60") (name "/CON1_P12") (class "Default")
      (node (ref "J42") (pin "12") (pinfunction "12_12") (pintype "bidirectional"))
    )
    (net (code "61") (name "/CON1_P13") (class "Default")
      (node (ref "J42") (pin "13") (pinfunction "13_13") (pintype "bidirectional"))
    )
    (net (code "62") (name "/CON1_P14") (class "Default")
      (node (ref "J42") (pin "14") (pinfunction "14_14") (pintype "bidirectional"))
    )
    (net (code "63") (name "/CON1_P15") (class "Default")
      (node (ref "J42") (pin "15") (pinfunction "15_15") (pintype "bidirectional"))
    )
    (net (code "64") (name "/CON1_P16") (class "Default")
      (node (ref "J42") (pin "16") (pinfunction "16_16") (pintype "bidirectional"))
    )
    (net (code "65") (name "/CON1_P17") (class "Default")
      (node (ref "J42") (pin "19") (pinfunction "19_19") (pintype "bidirectional"))
    )
    (net (code "66") (name "/CON1_P18") (class "Default")
      (node (ref "J42") (pin "20") (pinfunction "20_20") (pintype "bidirectional"))
    )
    (net (code "67") (name "/CON1_P19") (class "Default")
      (node (ref "J42") (pin "21") (pinfunction "21_21") (pintype "bidirectional"))
    )
    (net (code "68") (name "/CON1_P20") (class "Default")
      (node (ref "J42") (pin "22") (pinfunction "22_22") (pintype "bidirectional"))
    )
    (net (code "69") (name "/CON1_P21") (class "Default")
      (node (ref "J42") (pin "23") (pinfunction "23_23") (pintype "bidirectional"))
    )
    (net (code "70") (name "/CON1_P22") (class "Default")
      (node (ref "J42") (pin "24") (pinfunction "24_24") (pintype "bidirectional"))
    )
    (net (code "71") (name "/CON1_P23") (class "Default")
      (node (ref "J42") (pin "25") (pinfunction "25_25") (pintype "bidirectional"))
    )
    (net (code "72") (name "/CON1_P24") (class "Default")
      (node (ref "J42") (pin "26") (pinfunction "26_26") (pintype "bidirectional"))
    )
    (net (code "73") (name "/CON1_P25") (class "Default")
      (node (ref "J42") (pin "27") (pinfunction "27_27") (pintype "bidirectional"))
    )
    (net (code "74") (name "/CON1_P26") (class "Default")
      (node (ref "J42") (pin "28") (pinfunction "28_28") (pintype "bidirectional"))
    )
    (net (code "75") (name "/CON1_P27") (class "Default")
      (node (ref "J42") (pin "29") (pinfunction "29_29") (pintype "bidirectional"))
    )
    (net (code "76") (name "/CON1_P28") (class "Default")
      (node (ref "J42") (pin "30") (pinfunction "30_30") (pintype "bidirectional"))
    )
    (net (code "77") (name "/CON1_P29") (class "Default")
      (node (ref "J42") (pin "31") (pinfunction "31_31") (pintype "bidirectional"))
    )
    (net (code "78") (name "/CON1_P30") (class "Default")
      (node (ref "J42") (pin "32") (pinfunction "32_32") (pintype "bidirectional"))
    )
    (net (code "79") (name "/CON1_P31") (class "Default")
      (node (ref "J42") (pin "33") (pinfunction "33_33") (pintype "bidirectional"))
    )
    (net (code "80") (name "/CON1_P32") (class "Default")
      (node (ref "J42") (pin "34") (pinfunction "34_34") (pintype "bidirectional"))
    )
    (net (code "82") (name "/DATA0_N") (class "Default")
      (node (ref "J41") (pin "11") (pinfunction "11_11") (pintype "bidirectional"))
      (node (ref "R285") (pin "1") (pinfunction "1_1") (pintype "passive"))
    )
    (net (code "83") (name "/DATA0_P") (class "Default")
      (node (ref "J41") (pin "9") (pinfunction "9_9") (pintype "bidirectional"))
      (node (ref "R288") (pin "2") (pinfunction "2_2") (pintype "passive"))
    )
    (net (code "84") (name "/DATA1_N") (class "Default")
      (node (ref "J41") (pin "8") (pinfunction "8_8") (pintype "bidirectional"))
      (node (ref "R280") (pin "1") (pinfunction "1_1") (pintype "passive"))
    )
    (net (code "85") (name "/DATA1_P") (class "Default")
      (node (ref "J41") (pin "6") (pinfunction "6_6") (pintype "bidirectional"))
      (node (ref "R283") (pin "2") (pinfunction "2_2") (pintype "passive"))
    )
    (net (code "86") (name "/DATA2_N") (class "Default")
      (node (ref "J41") (pin "5") (pinfunction "5_5") (pintype "bidirectional"))
      (node (ref "R275") (pin "1") (pinfunction "1_1") (pintype "passive"))
    )
    (net (code "87") (name "/DATA2_P") (class "Default")
      (node (ref "J41") (pin "3") (pinfunction "3_3") (pintype "bidirectional"))
      (node (ref "R278") (pin "2") (pinfunction "2_2") (pintype "passive"))
    )
    (net (code "89") (name "/EN1_RX1") (class "Default")
      (node (ref "IC56") (pin "1") (pinfunction "QB_1") (pintype "tri_state"))
      (node (ref "R257") (pin "1") (pinfunction "1_1") (pintype "passive"))
    )
    (net (code "90") (name "/EN1_RX2") (class "Default")
      (node (ref "IC56") (pin "15") (pinfunction "QA_15") (pintype "tri_state"))
      (node (ref "R256") (pin "1") (pinfunction "1_1") (pintype "passive"))
    )
    (net (code "91") (name "/EN1_RX3") (class "Default")
      (node (ref "IC56") (pin "3") (pinfunction "QD_3") (pintype "tri_state"))
      (node (ref "R259") (pin "1") (pinfunction "1_1") (pintype "passive"))
    )
    (net (code "92") (name "/EN1_RX4") (class "Default")
      (node (ref "IC56") (pin "2") (pinfunction "QC_2") (pintype "tri_state"))
      (node (ref "R258") (pin "1") (pinfunction "1_1") (pintype "passive"))
    )
    (net (code "93") (name "/EN1_RX5") (class "Default")
      (node (ref "IC56") (pin "5") (pinfunction "QF_5") (pintype "tri_state"))
      (node (ref "R261") (pin "1") (pinfunction "1_1") (pintype "passive"))
    )
    (net (code "94") (name "/EN1_RX6") (class "Default")
      (node (ref "IC56") (pin "4") (pinfunction "QE_4") (pintype "tri_state"))
      (node (ref "R260") (pin "1") (pinfunction "1_1") (pintype "passive"))
    )
    (net (code "95") (name "/EN1_RX7") (class "Default")
      (node (ref "IC56") (pin "7") (pinfunction "QH_7") (pintype "tri_state"))
      (node (ref "R263") (pin "1") (pinfunction "1_1") (pintype "passive"))
    )
    (net (code "96") (name "/EN1_RX8") (class "Default")
      (node (ref "IC56") (pin "6") (pinfunction "QG_6") (pintype "tri_state"))
      (node (ref "R262") (pin "1") (pinfunction "1_1") (pintype "passive"))
    )
    (net (code "97") (name "/EN1_RX9") (class "Default")
      (node (ref "IC57") (pin "1") (pinfunction "QB_1") (pintype "tri_state"))
      (node (ref "R269") (pin "1") (pinfunction "1_1") (pintype "passive"))
    )
    (net (code "98") (name "/EN1_RX10") (class "Default")
      (node (ref "IC57") (pin "15") (pinfunction "QA_15") (pintype "tri_state"))
      (node (ref "R264") (pin "1") (pinfunction "1_1") (pintype "passive"))
    )
    (net (code "99") (name "/EN1_RX11") (class "Default")
      (node (ref "IC57") (pin "3") (pinfunction "QD_3") (pintype "tri_state"))
      (node (ref "R279") (pin "1") (pinfunction "1_1") (pintype "passive"))
    )
    (net (code "100") (name "/EN1_RX12") (class "Default")
      (node (ref "IC57") (pin "2") (pinfunction "QC_2") (pintype "tri_state"))
      (node (ref "R274") (pin "1") (pinfunction "1_1") (pintype "passive"))
    )
    (net (code "101") (name "/EN1_RX13") (class "Default")
      (node (ref "IC57") (pin "5") (pinfunction "QF_5") (pintype "tri_state"))
      (node (ref "R289") (pin "1") (pinfunction "1_1") (pintype "passive"))
    )
    (net (code "102") (name "/EN1_RX14") (class "Default")
      (node (ref "IC57") (pin "4") (pinfunction "QE_4") (pintype "tri_state"))
      (node (ref "R284") (pin "1") (pinfunction "1_1") (pintype "passive"))
    )
    (net (code "103") (name "/EN1_RX15") (class "Default")
      (node (ref "IC57") (pin "7") (pinfunction "QH_7") (pintype "tri_state"))
      (node (ref "R291") (pin "1") (pinfunction "1_1") (pintype "passive"))
    )
    (net (code "104") (name "/EN1_RX16") (class "Default")
      (node (ref "IC57") (pin "6") (pinfunction "QG_6") (pintype "tri_state"))
      (node (ref "R290") (pin "1") (pinfunction "1_1") (pintype "passive"))
    )
    (net (code "105") (name "/EN1_RX17") (class "Default")
      (node (ref "IC58") (pin "1") (pinfunction "QB_1") (pintype "tri_state"))
      (node (ref "R293") (pin "1") (pinfunction "1_1") (pintype "passive"))
    )
    (net (code "106") (name "/EN1_RX18") (class "Default")
      (node (ref "IC58") (pin "15") (pinfunction "QA_15") (pintype "tri_state"))
      (node (ref "R292") (pin "1") (pinfunction "1_1") (pintype "passive"))
    )
    (net (code "107") (name "/EN1_RX19") (class "Default")
      (node (ref "IC58") (pin "3") (pinfunction "QD_3") (pintype "tri_state"))
      (node (ref "R295") (pin "1") (pinfunction "1_1") (pintype "passive"))
    )
    (net (code "108") (name "/EN1_RX20") (class "Default")
      (node (ref "IC58") (pin "2") (pinfunction "QC_2") (pintype "tri_state"))
      (node (ref "R294") (pin "1") (pinfunction "1_1") (pintype "passive"))
    )
    (net (code "109") (name "/EN1_RX21") (class "Default")
      (node (ref "IC58") (pin "5") (pinfunction "QF_5") (pintype "tri_state"))
      (node (ref "R297") (pin "1") (pinfunction "1_1") (pintype "passive"))
    )
    (net (code "110") (name "/EN1_RX22") (class "Default")
      (node (ref "IC58") (pin "4") (pinfunction "QE_4") (pintype "tri_state"))
      (node (ref "R296") (pin "1") (pinfunction "1_1") (pintype "passive"))
    )
    (net (code "111") (name "/EN1_RX23") (class "Default")
      (node (ref "IC58") (pin "7") (pinfunction "QH_7") (pintype "tri_state"))
      (node (ref "R299") (pin "1") (pinfunction "1_1") (pintype "passive"))
    )
    (net (code "112") (name "/EN1_RX24") (class "Default")
      (node (ref "IC58") (pin "6") (pinfunction "QG_6") (pintype "tri_state"))
      (node (ref "R298") (pin "1") (pinfunction "1_1") (pintype "passive"))
    )
    (net (code "113") (name "/EN1_RX25") (class "Default")
      (node (ref "IC59") (pin "1") (pinfunction "QB_1") (pintype "tri_state"))
      (node (ref "R301") (pin "1") (pinfunction "1_1") (pintype "passive"))
    )
    (net (code "114") (name "/EN1_RX26") (class "Default")
      (node (ref "IC59") (pin "15") (pinfunction "QA_15") (pintype "tri_state"))
      (node (ref "R300") (pin "1") (pinfunction "1_1") (pintype "passive"))
    )
    (net (code "115") (name "/EN1_RX27") (class "Default")
      (node (ref "IC59") (pin "3") (pinfunction "QD_3") (pintype "tri_state"))
      (node (ref "R303") (pin "1") (pinfunction "1_1") (pintype "passive"))
    )
    (net (code "116") (name "/EN1_RX28") (class "Default")
      (node (ref "IC59") (pin "2") (pinfunction "QC_2") (pintype "tri_state"))
      (node (ref "R302") (pin "1") (pinfunction "1_1") (pintype "passive"))
    )
    (net (code "117") (name "/EN1_RX29") (class "Default")
      (node (ref "IC59") (pin "5") (pinfunction "QF_5") (pintype "tri_state"))
      (node (ref "R305") (pin "1") (pinfunction "1_1") (pintype "passive"))
    )
    (net (code "118") (name "/EN1_RX30") (class "Default")
      (node (ref "IC59") (pin "4") (pinfunction "QE_4") (pintype "tri_state"))
      (node (ref "R304") (pin "1") (pinfunction "1_1") (pintype "passive"))
    )
    (net (code "119") (name "/EN1_RX31") (class "Default")
      (node (ref "IC59") (pin "7") (pinfunction "QH_7") (pintype "tri_state"))
      (node (ref "R307") (pin "1") (pinfunction "1_1") (pintype "passive"))
    )
    (net (code "120") (name "/EN1_RX32") (class "Default")
      (node (ref "IC59") (pin "6") (pinfunction "QG_6") (pintype "tri_state"))
      (node (ref "R306") (pin "1") (pinfunction "1_1") (pintype "passive"))
    )
    (net (code "192") (name "/HEAC_N") (class "Default")
      (node (ref "J41") (pin "1") (pinfunction "1_1") (pintype "bidirectional"))
      (node (ref "R265") (pin "1") (pinfunction "1_1") (pintype "passive"))
    )
    (net (code "193") (name "/HEAC_P") (class "Default")
      (node (ref "J41") (pin "2") (pinfunction "2_2") (pintype "bidirectional"))
      (node (ref "R268") (pin "2") (pinfunction "2_2") (pintype "passive"))
    )
    (net (code "194") (name "/LATCH") (class "Default")
      (node (ref "IC56") (pin "12") (pinfunction "RCLK_12") (pintype "input"))
      (node (ref "IC57") (pin "12") (pinfunction "RCLK_12") (pintype "input"))
      (node (ref "IC58") (pin "12") (pinfunction "RCLK_12") (pintype "input"))
      (node (ref "IC59") (pin "12") (pinfunction "RCLK_12") (pintype "input"))
    )
    (net (code "196") (name "/REFIN") (class "Default")
      (node (ref "C149") (pin "2") (pinfunction "2_2") (pintype "passive"))
      (node (ref "IC55") (pin "1") (pinfunction "REFIN_1") (pintype "input"))
      (node (ref "R251") (pin "2") (pinfunction "2_2") (pintype "passive"))
      (node (ref "R253") (pin "2") (pinfunction "2_2") (pintype "passive"))
    )
    (net (code "197") (name "/SCL") (class "Default")
      (node (ref "IC60") (pin "3") (pinfunction "SCLIN_3") (pintype "bidirectional"))
    )
    (net (code "198") (name "/SCL_OUT") (class "Default")
      (node (ref "IC60") (pin "2") (pinfunction "SCLOUT_2") (pintype "bidirectional"))
      (node (ref "J41") (pin "17") (pinfunction "17_17") (pintype "bidirectional"))
      (node (ref "J42") (pin "17") (pinfunction "17_17") (pintype "bidirectional"))
      (node (ref "R311") (pin "1") (pinfunction "1_1") (pintype "passive"))
    )
    (net (code "199") (name "/SDA") (class "Default")
      (node (ref "IC60") (pin "6") (pinfunction "SDAIN_6") (pintype "bidirectional"))
    )
    (net (code "200") (name "/SDA_OUT") (class "Default")
      (node (ref "IC60") (pin "7") (pinfunction "SDAOUT_7") (pintype "bidirectional"))
      (node (ref "J41") (pin "18") (pinfunction "18_18") (pintype "bidirectional"))
      (node (ref "J42") (pin "51") (pinfunction "51_51") (pintype "bidirectional"))
      (node (ref "R310") (pin "1") (pinfunction "1_1") (pintype "passive"))
    )
    (net (code "201") (name "/SER_IN") (class "Default")
      (node (ref "IC56") (pin "14") (pinfunction "SER_14") (pintype "input"))
    )
    (net (code "202") (name "/SER_OUT") (class "Default")
      (node (ref "IC59") (pin "9") (pinfunction "QH'_9") (pintype "output"))
    )
    (net (code "203") (name "/SUP") (class "Default")
      (node (ref "F7") (pin "1") (pinfunction "1_1") (pintype "passive"))
      (node (ref "J42") (pin "18") (pinfunction "18_18") (pintype "bidirectional"))
      (node (ref "J42") (pin "52") (pinfunction "52_52") (pintype "bidirectional"))
    )
    (net (code "204") (name "/VOSNS") (class "Default")
      (node (ref "C150") (pin "1") (pinfunction "1_1") (pintype "passive"))
      (node (ref "IC55") (pin "5") (pinfunction "VOSNS_5") (pintype "input"))
      (node (ref "R252") (pin "2") (pinfunction "2_2") (pintype "passive"))
    )
    (net (code "205") (name "3P3VAUX") (class "Default")
      (node (ref "C164") (pin "2") (pinfunction "2_2") (pintype "passive"))
      (node (ref "IC60") (pin "8") (pinfunction "Vcc_8") (pintype "power_in"))
      (node (ref "R310") (pin "2") (pinfunction "2_2") (pintype "passive"))
      (node (ref "R311") (pin "2") (pinfunction "2_2") (pintype "passive"))
      (node (ref "R312") (pin "2") (pinfunction "2_2") (pintype "passive"))
    )
    (net (code "206") (name "GND") (class "Default")
      (node (ref "B10") (pin "1") (pinfunction "1_1") (pintype "bidirectional"))
      (node (ref "B11") (pin "1") (pinfunction "1_1") (pintype "bidirectional"))
      (node (ref "B8") (pin "1") (pinfunction "1_1") (pintype "bidirectional"))
      (node (ref "B9") (pin "1") (pinfunction "1_1") (pintype "bidirectional"))
      (node (ref "C146") (pin "1") (pinfunction "1_1") (pintype "passive"))
      (node (ref "C147") (pin "1") (pinfunction "1_1") (pintype "passive"))
      (node (ref "C148") (pin "1") (pinfunction "1_1") (pintype "passive"))
      (node (ref "C149") (pin "1") (pinfunction "1_1") (pintype "passive"))
      (node (ref "C150") (pin "2") (pinfunction "2_2") (pintype "passive"))
      (node (ref "C151") (pin "1") (pinfunction "1_1") (pintype "passive"))
      (node (ref "C152") (pin "1") (pinfunction "1_1") (pintype "passive"))
      (node (ref "C153") (pin "1") (pinfunction "1_1") (pintype "passive"))
      (node (ref "C154") (pin "1") (pinfunction "1_1") (pintype "passive"))
      (node (ref "C155") (pin "1") (pinfunction "1_1") (pintype "passive"))
      (node (ref "C156") (pin "1") (pinfunction "1_1") (pintype "passive"))
      (node (ref "C157") (pin "2") (pinfunction "2_2") (pintype "passive"))
      (node (ref "C158") (pin "2") (pinfunction "2_2") (pintype "passive"))
      (node (ref "C159") (pin "2") (pinfunction "2_2") (pintype "passive"))
      (node (ref "C160") (pin "2") (pinfunction "2_2") (pintype "passive"))
      (node (ref "C161") (pin "2") (pinfunction "2_2") (pintype "passive"))
      (node (ref "C162") (pin "2") (pinfunction "2_2") (pintype "passive"))
      (node (ref "C163") (pin "1") (pinfunction "1_1") (pintype "passive"))
      (node (ref "C164") (pin "1") (pinfunction "1_1") (pintype "passive"))
      (node (ref "IC55") (pin "11") (pinfunction "EP_11") (pintype "power_in"))
      (node (ref "IC55") (pin "4") (pinfunction "PGND_4") (pintype "power_in"))
      (node (ref "IC55") (pin "8") (pinfunction "GND_8") (pintype "power_in"))
      (node (ref "IC56") (pin "13") (pinfunction "~{OE}_13") (pintype "input"))
      (node (ref "IC56") (pin "8") (pinfunction "GND_8") (pintype "power_in"))
      (node (ref "IC57") (pin "13") (pinfunction "~{OE}_13") (pintype "input"))
      (node (ref "IC57") (pin "8") (pinfunction "GND_8") (pintype "power_in"))
      (node (ref "IC58") (pin "13") (pinfunction "~{OE}_13") (pintype "input"))
      (node (ref "IC58") (pin "8") (pinfunction "GND_8") (pintype "power_in"))
      (node (ref "IC59") (pin "13") (pinfunction "~{OE}_13") (pintype "input"))
      (node (ref "IC59") (pin "8") (pinfunction "GND_8") (pintype "power_in"))
      (node (ref "IC60") (pin "4") (pinfunction "GND_4") (pintype "power_in"))
      (node (ref "J41") (pin "10") (pinfunction "10_10") (pintype "bidirectional"))
      (node (ref "J41") (pin "13") (pinfunction "13_13") (pintype "bidirectional"))
      (node (ref "J41") (pin "16") (pinfunction "16_16") (pintype "bidirectional"))
      (node (ref "J41") (pin "4") (pinfunction "4_4") (pintype "bidirectional"))
      (node (ref "J41") (pin "7") (pinfunction "7_7") (pintype "bidirectional"))
      (node (ref "J41") (pin "SHIELD") (pinfunction "SHIELD_SHIELD") (pintype "power_in"))
      (node (ref "J42") (pin "69") (pinfunction "69_69") (pintype "passive"))
      (node (ref "J42") (pin "70") (pinfunction "70_70") (pintype "passive"))
      (node (ref "R253") (pin "1") (pinfunction "1_1") (pintype "passive"))
      (node (ref "R255") (pin "1") (pinfunction "1_1") (pintype "passive"))
      (node (ref "R256") (pin "2") (pinfunction "2_2") (pintype "passive"))
      (node (ref "R257") (pin "2") (pinfunction "2_2") (pintype "passive"))
      (node (ref "R258") (pin "2") (pinfunction "2_2") (pintype "passive"))
      (node (ref "R259") (pin "2") (pinfunction "2_2") (pintype "passive"))
      (node (ref "R260") (pin "2") (pinfunction "2_2") (pintype "passive"))
      (node (ref "R261") (pin "2") (pinfunction "2_2") (pintype "passive"))
      (node (ref "R262") (pin "2") (pinfunction "2_2") (pintype "passive"))
      (node (ref "R263") (pin "2") (pinfunction "2_2") (pintype "passive"))
      (node (ref "R264") (pin "2") (pinfunction "2_2") (pintype "passive"))
      (node (ref "R269") (pin "2") (pinfunction "2_2") (pintype "passive"))
      (node (ref "R274") (pin "2") (pinfunction "2_2") (pintype "passive"))
      (node (ref "R279") (pin "2") (pinfunction "2_2") (pintype "passive"))
      (node (ref "R284") (pin "2") (pinfunction "2_2") (pintype "passive"))
      (node (ref "R289") (pin "2") (pinfunction "2_2") (pintype "passive"))
      (node (ref "R290") (pin "2") (pinfunction "2_2") (pintype "passive"))
      (node (ref "R291") (pin "2") (pinfunction "2_2") (pintype "passive"))
      (node (ref "R292") (pin "2") (pinfunction "2_2") (pintype "passive"))
      (node (ref "R293") (pin "2") (pinfunction "2_2") (pintype "passive"))
      (node (ref "R294") (pin "2") (pinfunction "2_2") (pintype "passive"))
      (node (ref "R295") (pin "2") (pinfunction "2_2") (pintype "passive"))
      (node (ref "R296") (pin "2") (pinfunction "2_2") (pintype "passive"))
      (node (ref "R297") (pin "2") (pinfunction "2_2") (pintype "passive"))
      (node (ref "R298") (pin "2") (pinfunction "2_2") (pintype "passive"))
      (node (ref "R299") (pin "2") (pinfunction "2_2") (pintype "passive"))
      (node (ref "R300") (pin "2") (pinfunction "2_2") (pintype "passive"))
      (node (ref "R301") (pin "2") (pinfunction "2_2") (pintype "passive"))
      (node (ref "R302") (pin "2") (pinfunction "2_2") (pintype "passive"))
      (node (ref "R303") (pin "2") (pinfunction "2_2") (pintype "passive"))
      (node (ref "R304") (pin "2") (pinfunction "2_2") (pintype "passive"))
      (node (ref "R305") (pin "2") (pinfunction "2_2") (pintype "passive"))
      (node (ref "R306") (pin "2") (pinfunction "2_2") (pintype "passive"))
      (node (ref "R307") (pin "2") (pinfunction "2_2") (pintype "passive"))
      (node (ref "R308") (pin "2") (pinfunction "2_2") (pintype "passive"))
    )
    (net (code "207") (name "LVDS_REF") (class "Default")
      (node (ref "C147") (pin "2") (pinfunction "2_2") (pintype "passive"))
      (node (ref "C151") (pin "2") (pinfunction "2_2") (pintype "passive"))
      (node (ref "C152") (pin "2") (pinfunction "2_2") (pintype "passive"))
      (node (ref "IC55") (pin "3") (pinfunction "VO_3") (pintype "power_in"))
      (node (ref "IC55") (pin "6") (pinfunction "REFOUT_6") (pintype "output"))
      (node (ref "R252") (pin "1") (pinfunction "1_1") (pintype "passive"))
      (node (ref "R254") (pin "1") (pinfunction "1_1") (pintype "passive"))
      (node (ref "R255") (pin "2") (pinfunction "2_2") (pintype "passive"))
    )
    (net (code "208") (name "Net-(F6-Pad2)") (class "Default")
      (node (ref "F6") (pin "2") (pinfunction "2_2") (pintype "passive"))
      (node (ref "J41") (pin "19") (pinfunction "19_19") (pintype "bidirectional"))
    )
    (net (code "209") (name "Net-(IC56-QH')") (class "Default")
      (node (ref "IC56") (pin "9") (pinfunction "QH'_9") (pintype "output"))
      (node (ref "IC57") (pin "14") (pinfunction "SER_14") (pintype "input"))
    )
    (net (code "210") (name "Net-(IC57-QH')") (class "Default")
      (node (ref "IC57") (pin "9") (pinfunction "QH'_9") (pintype "output"))
      (node (ref "IC58") (pin "14") (pinfunction "SER_14") (pintype "input"))
    )
    (net (code "211") (name "Net-(IC58-QH')") (class "Default")
      (node (ref "IC58") (pin "9") (pinfunction "QH'_9") (pintype "output"))
      (node (ref "IC59") (pin "14") (pinfunction "SER_14") (pintype "input"))
    )
    (net (code "212") (name "Net-(IC60-EN)") (class "Default")
      (node (ref "C163") (pin "2") (pinfunction "2_2") (pintype "passive"))
      (node (ref "IC60") (pin "1") (pinfunction "EN_1") (pintype "input"))
      (node (ref "R309") (pin "2") (pinfunction "2_2") (pintype "passive"))
    )
    (net (code "213") (name "Net-(IC60-READY)") (class "Default")
      (node (ref "IC60") (pin "5") (pinfunction "READY_5") (pintype "output"))
      (node (ref "R312") (pin "1") (pinfunction "1_1") (pintype "passive"))
    )
    (net (code "214") (name "P3V3") (class "Default")
      (node (ref "C146") (pin "2") (pinfunction "2_2") (pintype "passive"))
      (node (ref "C148") (pin "2") (pinfunction "2_2") (pintype "passive"))
      (node (ref "C153") (pin "2") (pinfunction "2_2") (pintype "passive"))
      (node (ref "C154") (pin "2") (pinfunction "2_2") (pintype "passive"))
      (node (ref "C155") (pin "2") (pinfunction "2_2") (pintype "passive"))
      (node (ref "C156") (pin "2") (pinfunction "2_2") (pintype "passive"))
      (node (ref "C157") (pin "1") (pinfunction "1_1") (pintype "passive"))
      (node (ref "C158") (pin "1") (pinfunction "1_1") (pintype "passive"))
      (node (ref "C159") (pin "1") (pinfunction "1_1") (pintype "passive"))
      (node (ref "C160") (pin "1") (pinfunction "1_1") (pintype "passive"))
      (node (ref "C161") (pin "1") (pinfunction "1_1") (pintype "passive"))
      (node (ref "C162") (pin "1") (pinfunction "1_1") (pintype "passive"))
      (node (ref "F6") (pin "1") (pinfunction "1_1") (pintype "passive"))
      (node (ref "F7") (pin "2") (pinfunction "2_2") (pintype "passive"))
      (node (ref "IC55") (pin "10") (pinfunction "VIN_10") (pintype "input"))
      (node (ref "IC55") (pin "2") (pinfunction "VLDOIN_2") (pintype "input"))
      (node (ref "IC55") (pin "7") (pinfunction "EN_7") (pintype "input"))
      (node (ref "IC56") (pin "10") (pinfunction "~{SRCLR}_10") (pintype "input"))
      (node (ref "IC56") (pin "16") (pinfunction "VCC_16") (pintype "power_in"))
      (node (ref "IC57") (pin "10") (pinfunction "~{SRCLR}_10") (pintype "input"))
      (node (ref "IC57") (pin "16") (pinfunction "VCC_16") (pintype "power_in"))
      (node (ref "IC58") (pin "10") (pinfunction "~{SRCLR}_10") (pintype "input"))
      (node (ref "IC58") (pin "16") (pinfunction "VCC_16") (pintype "power_in"))
      (node (ref "IC59") (pin "10") (pinfunction "~{SRCLR}_10") (pintype "input"))
      (node (ref "IC59") (pin "16") (pinfunction "VCC_16") (pintype "power_in"))
      (node (ref "R251") (pin "1") (pinfunction "1_1") (pintype "passive"))
      (node (ref "R254") (pin "2") (pinfunction "2_2") (pintype "passive"))
      (node (ref "R308") (pin "1") (pinfunction "1_1") (pintype "passive"))
      (node (ref "R309") (pin "1") (pinfunction "1_1") (pintype "passive"))
    )
    (net (code "215") (name "unconnected-(IC55-PGOOD-Pad9)") (class "Default")
      (node (ref "IC55") (pin "9") (pinfunction "PGOOD_9") (pintype "output"))
    )
    (net (code "216") (name "unconnected-(J41-Pad15)") (class "Default")
      (node (ref "J41") (pin "15") (pinfunction "15_15") (pintype "bidirectional"))
    )
  )
)
